# g3d2_ctrl_2.net
KiCad netlist of a schematic drawn in EAGLE
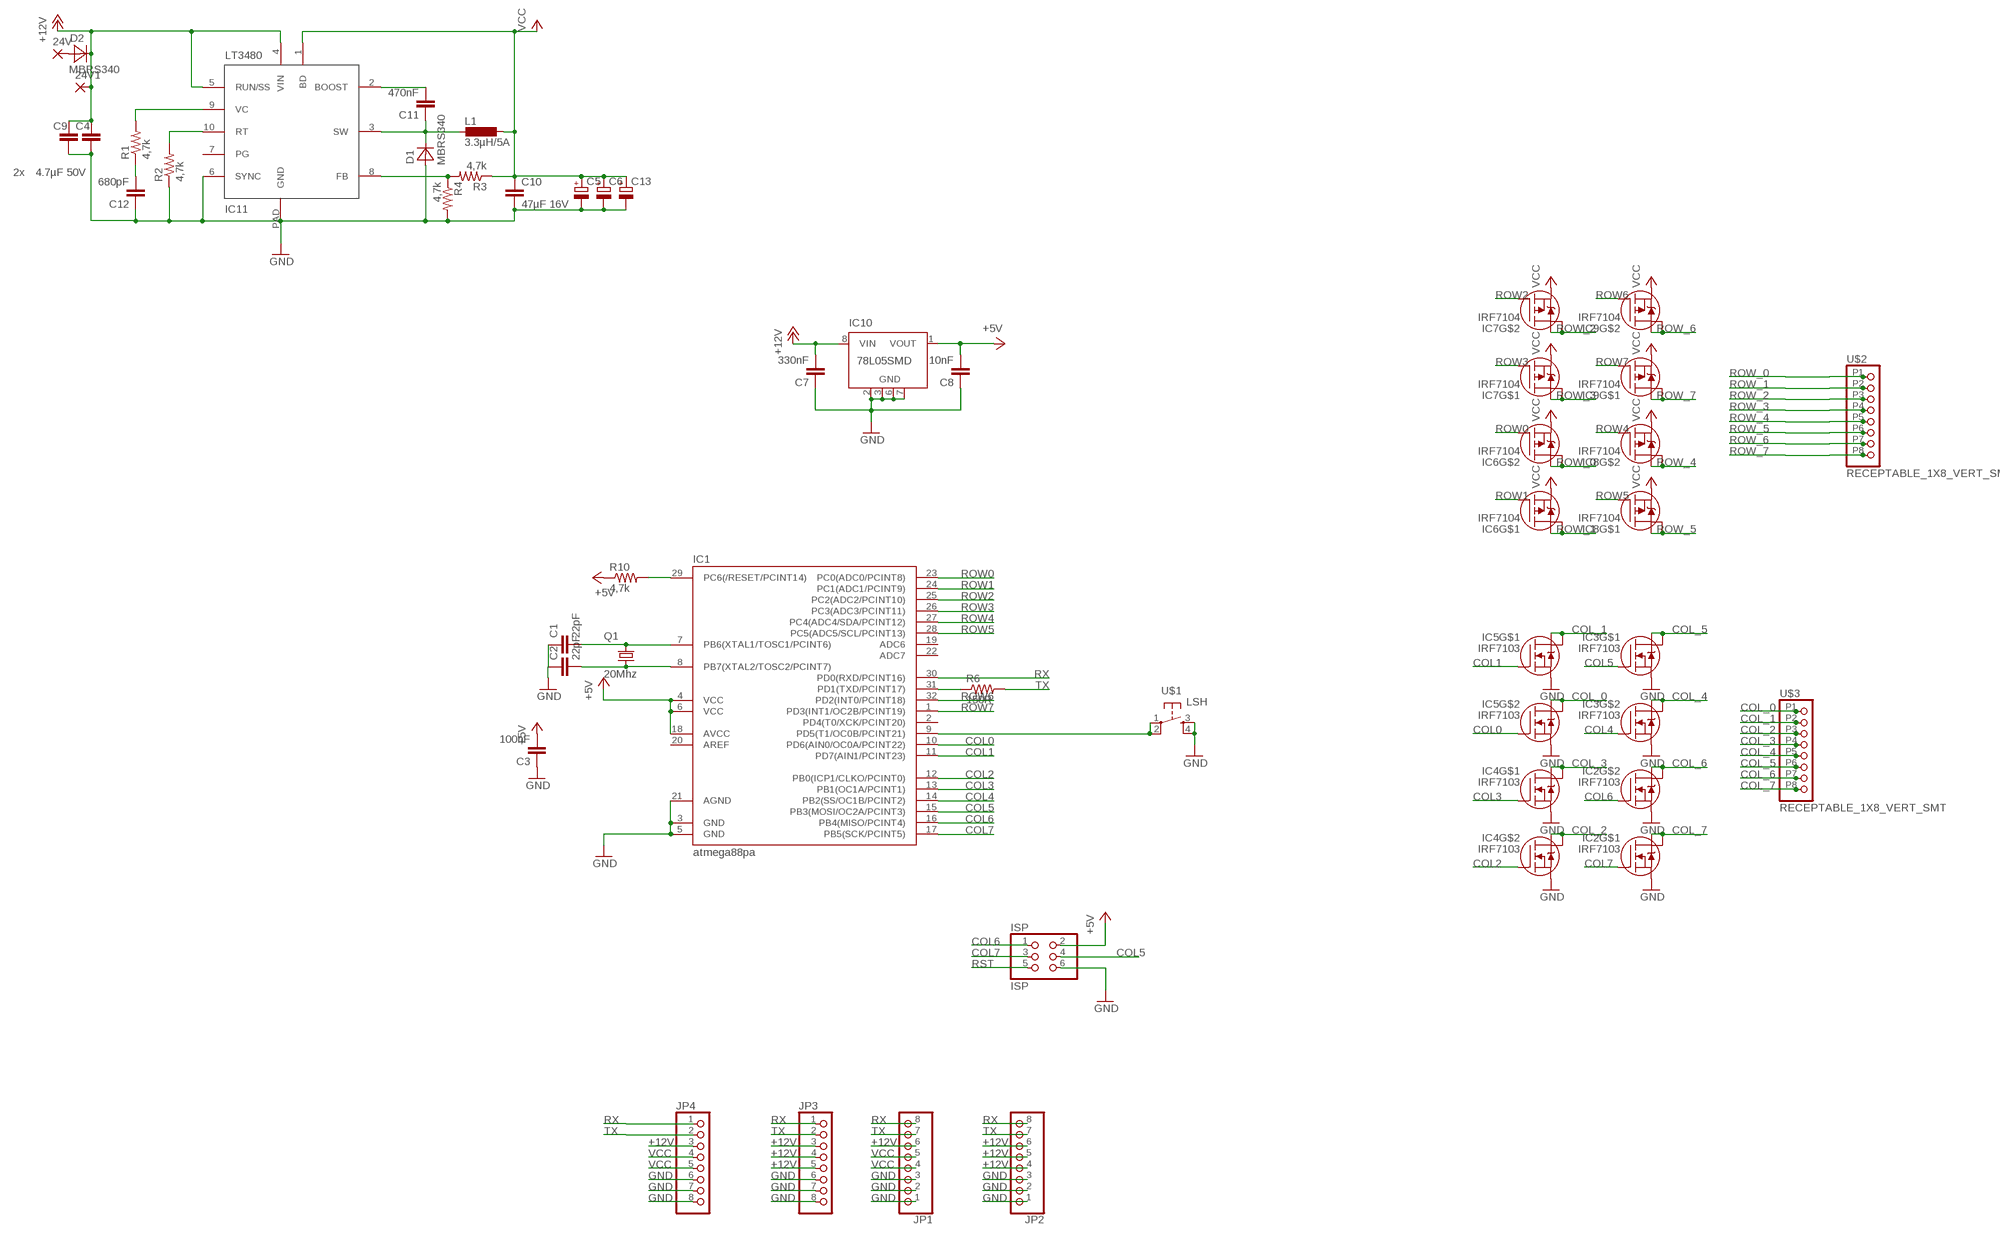
[diagram p0: schematic, sheet 1]

(export (version "E")
  (design (tool "Eeschema 10.0.6"))
  (components
    (comp (ref "24V")
      (value "SMD5")
      (footprint "eagle-import:SMD2,54-5,08")
      (libsource (lib "eagle-import") (part "SMD5"))
    )
    (comp (ref "24V1")
      (value "SMD5")
      (footprint "eagle-import:SMD2,54-5,08")
      (libsource (lib "eagle-import") (part "SMD5"))
    )
    (comp (ref "C1")
      (value "22pF")
      (footprint "eagle-import:0805")
      (libsource (lib "eagle-import") (part "CAP0805"))
    )
    (comp (ref "C2")
      (value "22pF")
      (footprint "eagle-import:0805")
      (libsource (lib "eagle-import") (part "CAP0805"))
    )
    (comp (ref "C3")
      (value "100nF")
      (footprint "eagle-import:0805")
      (libsource (lib "eagle-import") (part "CAP0805"))
    )
    (comp (ref "C4")
      (value "4.7µF 50V")
      (footprint "eagle-import:1210")
      (libsource (lib "eagle-import") (part "CAP1210"))
    )
    (comp (ref "C5")
      (value "CPOL-EUSMCD")
      (footprint "eagle-import:SMC_D")
      (libsource (lib "eagle-import") (part "CPOL-EUSMCD"))
    )
    (comp (ref "C6")
      (value "CPOL-EUSMCD")
      (footprint "eagle-import:SMC_D")
      (libsource (lib "eagle-import") (part "CPOL-EUSMCD"))
    )
    (comp (ref "C7")
      (value "330nF")
      (footprint "eagle-import:0805")
      (libsource (lib "eagle-import") (part "CAP0805"))
    )
    (comp (ref "C8")
      (value "10nF")
      (footprint "eagle-import:0805")
      (libsource (lib "eagle-import") (part "CAP0805"))
    )
    (comp (ref "C9")
      (value "4.7µF 50V")
      (footprint "eagle-import:1210")
      (libsource (lib "eagle-import") (part "CAP1210"))
    )
    (comp (ref "C10")
      (value "47µF 16V")
      (footprint "eagle-import:1210")
      (libsource (lib "eagle-import") (part "CAP1210"))
    )
    (comp (ref "C11")
      (value "470nF")
      (footprint "eagle-import:0805")
      (libsource (lib "eagle-import") (part "CAP0805"))
    )
    (comp (ref "C12")
      (value "680pF")
      (footprint "eagle-import:0805")
      (libsource (lib "eagle-import") (part "CAP0805"))
    )
    (comp (ref "C13")
      (value "CPOL-EUSMCD")
      (footprint "eagle-import:SMC_D")
      (libsource (lib "eagle-import") (part "CPOL-EUSMCD"))
    )
    (comp (ref "D1")
      (value "MBRS340")
      (footprint "eagle-import:DO214AB")
      (libsource (lib "eagle-import") (part "MBRS340"))
    )
    (comp (ref "D2")
      (value "MBRS340")
      (footprint "eagle-import:DO214AB")
      (libsource (lib "eagle-import") (part "MBRS340"))
    )
    (comp (ref "IC1")
      (value "atmega88pa")
      (footprint "eagle-import:TQFP32-08")
      (libsource (lib "eagle-import") (part "MEGA48/88/168-AU"))
    )
    (comp (ref "IC2")
      (value "IRF7103")
      (footprint "eagle-import:SO8-2")
      (libsource (lib "eagle-import") (part "IRF7103"))
    )
    (comp (ref "IC3")
      (value "IRF7103")
      (footprint "eagle-import:SO8-2")
      (libsource (lib "eagle-import") (part "IRF7103"))
    )
    (comp (ref "IC4")
      (value "IRF7103")
      (footprint "eagle-import:SO8-2")
      (libsource (lib "eagle-import") (part "IRF7103"))
    )
    (comp (ref "IC5")
      (value "IRF7103")
      (footprint "eagle-import:SO8-2")
      (libsource (lib "eagle-import") (part "IRF7103"))
    )
    (comp (ref "IC6")
      (value "IRF7104")
      (footprint "eagle-import:SO8-2")
      (libsource (lib "eagle-import") (part "IRF7104"))
    )
    (comp (ref "IC7")
      (value "IRF7104")
      (footprint "eagle-import:SO8-2")
      (libsource (lib "eagle-import") (part "IRF7104"))
    )
    (comp (ref "IC8")
      (value "IRF7104")
      (footprint "eagle-import:SO8-2")
      (libsource (lib "eagle-import") (part "IRF7104"))
    )
    (comp (ref "IC9")
      (value "IRF7104")
      (footprint "eagle-import:SO8-2")
      (libsource (lib "eagle-import") (part "IRF7104"))
    )
    (comp (ref "IC10")
      (value "78L05SMD")
      (footprint "eagle-import:SO08")
      (libsource (lib "eagle-import") (part "78LSMD05"))
    )
    (comp (ref "IC11")
      (value "LT3972")
      (footprint "eagle-import:MSOP10-PAD")
      (libsource (lib "eagle-import") (part "LT3480"))
    )
    (comp (ref "ISP")
      (value "ISP")
      (footprint "eagle-import:2X03")
      (libsource (lib "eagle-import") (part "PINHD-2X03_2.54"))
    )
    (comp (ref "JP1")
      (value "PINHD-1X08_2.54-SMD-90°")
      (footprint "eagle-import:1X08SMD_90")
      (libsource (lib "eagle-import") (part "PINHD-1X08_2.54-SMD-90°"))
    )
    (comp (ref "JP2")
      (value "PINHD-1X08_2.54-SMD-90°")
      (footprint "eagle-import:1X08SMD_90")
      (libsource (lib "eagle-import") (part "PINHD-1X08_2.54-SMD-90°"))
    )
    (comp (ref "JP3")
      (value "PINHD-1X08_2.54-SMD-90°")
      (footprint "eagle-import:1X08SMD_90")
      (libsource (lib "eagle-import") (part "PINHD-1X08_2.54-SMD-90°"))
    )
    (comp (ref "JP4")
      (value "PINHD-1X08_2.54-SMD-90°")
      (footprint "eagle-import:1X08SMD_90")
      (libsource (lib "eagle-import") (part "PINHD-1X08_2.54-SMD-90°"))
    )
    (comp (ref "L1")
      (value "3.3µH/5A")
      (footprint "eagle-import:DO3316P")
      (libsource (lib "eagle-import") (part "DO3316P"))
    )
    (comp (ref "Q1")
      (value "20Mhz")
      (footprint "eagle-import:X22")
      (libsource (lib "eagle-import") (part "X22-OSCILLATOR"))
    )
    (comp (ref "R1")
      (value "4,7k")
      (footprint "eagle-import:0805")
      (libsource (lib "eagle-import") (part "RESISTOR"))
    )
    (comp (ref "R2")
      (value "4,7k")
      (footprint "eagle-import:0805")
      (libsource (lib "eagle-import") (part "RESISTOR"))
    )
    (comp (ref "R3")
      (value "4,7k")
      (footprint "eagle-import:0805")
      (libsource (lib "eagle-import") (part "RESISTOR"))
    )
    (comp (ref "R4")
      (value "4,7k")
      (footprint "eagle-import:0805")
      (libsource (lib "eagle-import") (part "RESISTOR"))
    )
    (comp (ref "R6")
      (value "150R")
      (footprint "eagle-import:0805")
      (libsource (lib "eagle-import") (part "RESISTOR"))
    )
    (comp (ref "R10")
      (value "4,7k")
      (footprint "eagle-import:0805")
      (libsource (lib "eagle-import") (part "RESISTOR"))
    )
    (comp (ref "U$1")
      (value "LSH")
      (footprint "eagle-import:LSH")
      (libsource (lib "eagle-import") (part "LSH"))
    )
    (comp (ref "U$2")
      (value "RECEPTABLE_1X8_VERT_SMT")
      (footprint "eagle-import:RECEPTABLE_1X8_VERT_SMT")
      (libsource (lib "eagle-import") (part "RECEPTABLE_1X8_VERT_SMT"))
    )
    (comp (ref "U$3")
      (value "RECEPTABLE_1X8_VERT_SMT")
      (footprint "eagle-import:RECEPTABLE_1X8_VERT_SMT")
      (libsource (lib "eagle-import") (part "RECEPTABLE_1X8_VERT_SMT"))
    )
  )
  (nets
    (net (code "1") (name "+5V") (class "Default")
      (node (ref "C3") (pin "2") (pinfunction "2_2") (pintype "passive"))
      (node (ref "C8") (pin "2") (pinfunction "2_2") (pintype "passive"))
      (node (ref "IC1") (pin "18") (pinfunction "AVCC_18") (pintype "passive"))
      (node (ref "IC1") (pin "4") (pinfunction "VCC_4") (pintype "power_in"))
      (node (ref "IC1") (pin "6") (pinfunction "VCC_6") (pintype "power_in"))
      (node (ref "IC10") (pin "1") (pinfunction "VOUT_1") (pintype "output"))
      (node (ref "ISP") (pin "2") (pinfunction "2_2") (pintype "passive"))
      (node (ref "R10") (pin "1") (pinfunction "1_1") (pintype "passive"))
    )
    (net (code "2") (name "+12V") (class "Default")
      (node (ref "24V1") (pin "1") (pinfunction "P_1") (pintype "passive"))
      (node (ref "C4") (pin "1") (pinfunction "1_1") (pintype "passive"))
      (node (ref "C7") (pin "2") (pinfunction "2_2") (pintype "passive"))
      (node (ref "C9") (pin "1") (pinfunction "1_1") (pintype "passive"))
      (node (ref "D2") (pin "K") (pinfunction "C_K") (pintype "passive"))
      (node (ref "IC10") (pin "8") (pinfunction "VIN_8") (pintype "passive"))
      (node (ref "IC11") (pin "4") (pinfunction "VIN_4") (pintype "bidirectional"))
      (node (ref "IC11") (pin "5") (pinfunction "RUN/SS_5") (pintype "bidirectional"))
      (node (ref "JP1") (pin "6") (pinfunction "6_6") (pintype "passive"))
      (node (ref "JP2") (pin "4") (pinfunction "4_4") (pintype "passive"))
      (node (ref "JP2") (pin "5") (pinfunction "5_5") (pintype "passive"))
      (node (ref "JP2") (pin "6") (pinfunction "6_6") (pintype "passive"))
      (node (ref "JP3") (pin "3") (pinfunction "3_3") (pintype "passive"))
      (node (ref "JP3") (pin "4") (pinfunction "4_4") (pintype "passive"))
      (node (ref "JP3") (pin "5") (pinfunction "5_5") (pintype "passive"))
      (node (ref "JP4") (pin "3") (pinfunction "3_3") (pintype "passive"))
    )
    (net (code "3") (name "/COL0") (class "Default")
      (node (ref "IC1") (pin "10") (pinfunction "PD6(AIN0/OC0A/PCINT22)_10") (pintype "bidirectional"))
      (node (ref "IC5") (pin "4") (pinfunction "G_4") (pintype "bidirectional"))
    )
    (net (code "4") (name "/COL1") (class "Default")
      (node (ref "IC1") (pin "11") (pinfunction "PD7(AIN1/PCINT23)_11") (pintype "bidirectional"))
      (node (ref "IC5") (pin "2") (pinfunction "G_2") (pintype "bidirectional"))
    )
    (net (code "5") (name "/COL2") (class "Default")
      (node (ref "IC1") (pin "12") (pinfunction "PB0(ICP1/CLKO/PCINT0)_12") (pintype "bidirectional"))
      (node (ref "IC4") (pin "4") (pinfunction "G_4") (pintype "bidirectional"))
    )
    (net (code "6") (name "/COL3") (class "Default")
      (node (ref "IC1") (pin "13") (pinfunction "PB1(OC1A/PCINT1)_13") (pintype "bidirectional"))
      (node (ref "IC4") (pin "2") (pinfunction "G_2") (pintype "bidirectional"))
    )
    (net (code "7") (name "/COL4") (class "Default")
      (node (ref "IC1") (pin "14") (pinfunction "PB2(SS/OC1B/PCINT2)_14") (pintype "bidirectional"))
      (node (ref "IC3") (pin "4") (pinfunction "G_4") (pintype "bidirectional"))
    )
    (net (code "8") (name "/COL5") (class "Default")
      (node (ref "IC1") (pin "15") (pinfunction "PB3(MOSI/OC2A/PCINT3)_15") (pintype "bidirectional"))
      (node (ref "IC3") (pin "2") (pinfunction "G_2") (pintype "bidirectional"))
      (node (ref "ISP") (pin "4") (pinfunction "4_4") (pintype "passive"))
    )
    (net (code "9") (name "/COL6") (class "Default")
      (node (ref "IC1") (pin "16") (pinfunction "PB4(MISO/PCINT4)_16") (pintype "bidirectional"))
      (node (ref "IC2") (pin "4") (pinfunction "G_4") (pintype "bidirectional"))
      (node (ref "ISP") (pin "1") (pinfunction "1_1") (pintype "passive"))
    )
    (net (code "10") (name "/COL7") (class "Default")
      (node (ref "IC1") (pin "17") (pinfunction "PB5(SCK/PCINT5)_17") (pintype "bidirectional"))
      (node (ref "IC2") (pin "2") (pinfunction "G_2") (pintype "bidirectional"))
      (node (ref "ISP") (pin "3") (pinfunction "3_3") (pintype "passive"))
    )
    (net (code "11") (name "/COL_0") (class "Default")
      (node (ref "IC5") (pin "5") (pinfunction "D_5") (pintype "bidirectional"))
      (node (ref "IC5") (pin "6") (pinfunction "D_6") (pintype "bidirectional"))
      (node (ref "U$3") (pin "P1") (pinfunction "1_P1") (pintype "passive"))
    )
    (net (code "12") (name "/COL_1") (class "Default")
      (node (ref "IC5") (pin "7") (pinfunction "D_7") (pintype "bidirectional"))
      (node (ref "IC5") (pin "8") (pinfunction "D_8") (pintype "bidirectional"))
      (node (ref "U$3") (pin "P2") (pinfunction "2_P2") (pintype "passive"))
    )
    (net (code "13") (name "/COL_2") (class "Default")
      (node (ref "IC4") (pin "5") (pinfunction "D_5") (pintype "bidirectional"))
      (node (ref "IC4") (pin "6") (pinfunction "D_6") (pintype "bidirectional"))
      (node (ref "U$3") (pin "P3") (pinfunction "3_P3") (pintype "passive"))
    )
    (net (code "14") (name "/COL_3") (class "Default")
      (node (ref "IC4") (pin "7") (pinfunction "D_7") (pintype "bidirectional"))
      (node (ref "IC4") (pin "8") (pinfunction "D_8") (pintype "bidirectional"))
      (node (ref "U$3") (pin "P4") (pinfunction "4_P4") (pintype "passive"))
    )
    (net (code "15") (name "/COL_4") (class "Default")
      (node (ref "IC3") (pin "5") (pinfunction "D_5") (pintype "bidirectional"))
      (node (ref "IC3") (pin "6") (pinfunction "D_6") (pintype "bidirectional"))
      (node (ref "U$3") (pin "P5") (pinfunction "5_P5") (pintype "passive"))
    )
    (net (code "16") (name "/COL_5") (class "Default")
      (node (ref "IC3") (pin "7") (pinfunction "D_7") (pintype "bidirectional"))
      (node (ref "IC3") (pin "8") (pinfunction "D_8") (pintype "bidirectional"))
      (node (ref "U$3") (pin "P6") (pinfunction "6_P6") (pintype "passive"))
    )
    (net (code "17") (name "/COL_6") (class "Default")
      (node (ref "IC2") (pin "5") (pinfunction "D_5") (pintype "bidirectional"))
      (node (ref "IC2") (pin "6") (pinfunction "D_6") (pintype "bidirectional"))
      (node (ref "U$3") (pin "P7") (pinfunction "7_P7") (pintype "passive"))
    )
    (net (code "18") (name "/COL_7") (class "Default")
      (node (ref "IC2") (pin "7") (pinfunction "D_7") (pintype "bidirectional"))
      (node (ref "IC2") (pin "8") (pinfunction "D_8") (pintype "bidirectional"))
      (node (ref "U$3") (pin "P8") (pinfunction "8_P8") (pintype "passive"))
    )
    (net (code "19") (name "/ROW0") (class "Default")
      (node (ref "IC1") (pin "23") (pinfunction "PC0(ADC0/PCINT8)_23") (pintype "bidirectional"))
      (node (ref "IC6") (pin "4") (pinfunction "G_4") (pintype "bidirectional"))
    )
    (net (code "20") (name "/ROW1") (class "Default")
      (node (ref "IC1") (pin "24") (pinfunction "PC1(ADC1/PCINT9)_24") (pintype "bidirectional"))
      (node (ref "IC6") (pin "2") (pinfunction "G_2") (pintype "bidirectional"))
    )
    (net (code "21") (name "/ROW2") (class "Default")
      (node (ref "IC1") (pin "25") (pinfunction "PC2(ADC2/PCINT10)_25") (pintype "bidirectional"))
      (node (ref "IC7") (pin "4") (pinfunction "G_4") (pintype "bidirectional"))
    )
    (net (code "22") (name "/ROW3") (class "Default")
      (node (ref "IC1") (pin "26") (pinfunction "PC3(ADC3/PCINT11)_26") (pintype "bidirectional"))
      (node (ref "IC7") (pin "2") (pinfunction "G_2") (pintype "bidirectional"))
    )
    (net (code "23") (name "/ROW4") (class "Default")
      (node (ref "IC1") (pin "27") (pinfunction "PC4(ADC4/SDA/PCINT12)_27") (pintype "bidirectional"))
      (node (ref "IC8") (pin "4") (pinfunction "G_4") (pintype "bidirectional"))
    )
    (net (code "24") (name "/ROW5") (class "Default")
      (node (ref "IC1") (pin "28") (pinfunction "PC5(ADC5/SCL/PCINT13)_28") (pintype "bidirectional"))
      (node (ref "IC8") (pin "2") (pinfunction "G_2") (pintype "bidirectional"))
    )
    (net (code "25") (name "/ROW6") (class "Default")
      (node (ref "IC1") (pin "32") (pinfunction "PD2(INT0/PCINT18)_32") (pintype "bidirectional"))
      (node (ref "IC9") (pin "4") (pinfunction "G_4") (pintype "bidirectional"))
    )
    (net (code "26") (name "/ROW7") (class "Default")
      (node (ref "IC1") (pin "1") (pinfunction "PD3(INT1/OC2B/PCINT19)_1") (pintype "bidirectional"))
      (node (ref "IC9") (pin "2") (pinfunction "G_2") (pintype "bidirectional"))
    )
    (net (code "27") (name "/ROW_0") (class "Default")
      (node (ref "IC6") (pin "5") (pinfunction "D_5") (pintype "bidirectional"))
      (node (ref "IC6") (pin "6") (pinfunction "D_6") (pintype "bidirectional"))
      (node (ref "U$2") (pin "P1") (pinfunction "1_P1") (pintype "passive"))
    )
    (net (code "28") (name "/ROW_1") (class "Default")
      (node (ref "IC6") (pin "7") (pinfunction "D_7") (pintype "bidirectional"))
      (node (ref "IC6") (pin "8") (pinfunction "D_8") (pintype "bidirectional"))
      (node (ref "U$2") (pin "P2") (pinfunction "2_P2") (pintype "passive"))
    )
    (net (code "29") (name "/ROW_2") (class "Default")
      (node (ref "IC7") (pin "5") (pinfunction "D_5") (pintype "bidirectional"))
      (node (ref "IC7") (pin "6") (pinfunction "D_6") (pintype "bidirectional"))
      (node (ref "U$2") (pin "P3") (pinfunction "3_P3") (pintype "passive"))
    )
    (net (code "30") (name "/ROW_3") (class "Default")
      (node (ref "IC7") (pin "7") (pinfunction "D_7") (pintype "bidirectional"))
      (node (ref "IC7") (pin "8") (pinfunction "D_8") (pintype "bidirectional"))
      (node (ref "U$2") (pin "P4") (pinfunction "4_P4") (pintype "passive"))
    )
    (net (code "31") (name "/ROW_4") (class "Default")
      (node (ref "IC8") (pin "5") (pinfunction "D_5") (pintype "bidirectional"))
      (node (ref "IC8") (pin "6") (pinfunction "D_6") (pintype "bidirectional"))
      (node (ref "U$2") (pin "P5") (pinfunction "5_P5") (pintype "passive"))
    )
    (net (code "32") (name "/ROW_5") (class "Default")
      (node (ref "IC8") (pin "7") (pinfunction "D_7") (pintype "bidirectional"))
      (node (ref "IC8") (pin "8") (pinfunction "D_8") (pintype "bidirectional"))
      (node (ref "U$2") (pin "P6") (pinfunction "6_P6") (pintype "passive"))
    )
    (net (code "33") (name "/ROW_6") (class "Default")
      (node (ref "IC9") (pin "5") (pinfunction "D_5") (pintype "bidirectional"))
      (node (ref "IC9") (pin "6") (pinfunction "D_6") (pintype "bidirectional"))
      (node (ref "U$2") (pin "P7") (pinfunction "7_P7") (pintype "passive"))
    )
    (net (code "34") (name "/ROW_7") (class "Default")
      (node (ref "IC9") (pin "7") (pinfunction "D_7") (pintype "bidirectional"))
      (node (ref "IC9") (pin "8") (pinfunction "D_8") (pintype "bidirectional"))
      (node (ref "U$2") (pin "P8") (pinfunction "8_P8") (pintype "passive"))
    )
    (net (code "35") (name "/RST") (class "Default")
      (node (ref "IC1") (pin "29") (pinfunction "PC6(/RESET/PCINT14)_29") (pintype "bidirectional"))
      (node (ref "ISP") (pin "5") (pinfunction "5_5") (pintype "passive"))
      (node (ref "R10") (pin "2") (pinfunction "2_2") (pintype "passive"))
    )
    (net (code "36") (name "/RX") (class "Default")
      (node (ref "IC1") (pin "30") (pinfunction "PD0(RXD/PCINT16)_30") (pintype "bidirectional"))
      (node (ref "JP1") (pin "8") (pinfunction "8_8") (pintype "passive"))
      (node (ref "JP2") (pin "8") (pinfunction "8_8") (pintype "passive"))
      (node (ref "JP3") (pin "1") (pinfunction "1_1") (pintype "passive"))
      (node (ref "JP4") (pin "1") (pinfunction "1_1") (pintype "passive"))
    )
    (net (code "37") (name "/TX") (class "Default")
      (node (ref "JP1") (pin "7") (pinfunction "7_7") (pintype "passive"))
      (node (ref "JP2") (pin "7") (pinfunction "7_7") (pintype "passive"))
      (node (ref "JP3") (pin "2") (pinfunction "2_2") (pintype "passive"))
      (node (ref "JP4") (pin "2") (pinfunction "2_2") (pintype "passive"))
      (node (ref "R6") (pin "2") (pinfunction "2_2") (pintype "passive"))
    )
    (net (code "38") (name "GND") (class "Default")
      (node (ref "C1") (pin "1") (pinfunction "1_1") (pintype "passive"))
      (node (ref "C10") (pin "2") (pinfunction "2_2") (pintype "passive"))
      (node (ref "C12") (pin "1") (pinfunction "1_1") (pintype "passive"))
      (node (ref "C13") (pin "-") (pinfunction "-_-") (pintype "passive"))
      (node (ref "C2") (pin "1") (pinfunction "1_1") (pintype "passive"))
      (node (ref "C3") (pin "1") (pinfunction "1_1") (pintype "passive"))
      (node (ref "C4") (pin "2") (pinfunction "2_2") (pintype "passive"))
      (node (ref "C5") (pin "-") (pinfunction "-_-") (pintype "passive"))
      (node (ref "C6") (pin "-") (pinfunction "-_-") (pintype "passive"))
      (node (ref "C7") (pin "1") (pinfunction "1_1") (pintype "passive"))
      (node (ref "C8") (pin "1") (pinfunction "1_1") (pintype "passive"))
      (node (ref "C9") (pin "2") (pinfunction "2_2") (pintype "passive"))
      (node (ref "D1") (pin "A") (pinfunction "A_A") (pintype "passive"))
      (node (ref "IC1") (pin "21") (pinfunction "AGND_21") (pintype "power_in"))
      (node (ref "IC1") (pin "3") (pinfunction "GND_3") (pintype "power_in"))
      (node (ref "IC1") (pin "5") (pinfunction "GND_5") (pintype "power_in"))
      (node (ref "IC10") (pin "2") (pinfunction "GND_2") (pintype "power_in"))
      (node (ref "IC10") (pin "3") (pinfunction "GND_3") (pintype "power_in"))
      (node (ref "IC10") (pin "6") (pinfunction "GND_6") (pintype "power_in"))
      (node (ref "IC10") (pin "7") (pinfunction "GND_7") (pintype "power_in"))
      (node (ref "IC11") (pin "6") (pinfunction "SYNC_6") (pintype "bidirectional"))
      (node (ref "IC11") (pin "PAD") (pinfunction "GND_PAD") (pintype "bidirectional"))
      (node (ref "IC2") (pin "1") (pinfunction "S_1") (pintype "bidirectional"))
      (node (ref "IC2") (pin "3") (pinfunction "S_3") (pintype "bidirectional"))
      (node (ref "IC3") (pin "1") (pinfunction "S_1") (pintype "bidirectional"))
      (node (ref "IC3") (pin "3") (pinfunction "S_3") (pintype "bidirectional"))
      (node (ref "IC4") (pin "1") (pinfunction "S_1") (pintype "bidirectional"))
      (node (ref "IC4") (pin "3") (pinfunction "S_3") (pintype "bidirectional"))
      (node (ref "IC5") (pin "1") (pinfunction "S_1") (pintype "bidirectional"))
      (node (ref "IC5") (pin "3") (pinfunction "S_3") (pintype "bidirectional"))
      (node (ref "ISP") (pin "6") (pinfunction "6_6") (pintype "passive"))
      (node (ref "JP1") (pin "1") (pinfunction "1_1") (pintype "passive"))
      (node (ref "JP1") (pin "2") (pinfunction "2_2") (pintype "passive"))
      (node (ref "JP1") (pin "3") (pinfunction "3_3") (pintype "passive"))
      (node (ref "JP2") (pin "1") (pinfunction "1_1") (pintype "passive"))
      (node (ref "JP2") (pin "2") (pinfunction "2_2") (pintype "passive"))
      (node (ref "JP2") (pin "3") (pinfunction "3_3") (pintype "passive"))
      (node (ref "JP3") (pin "6") (pinfunction "6_6") (pintype "passive"))
      (node (ref "JP3") (pin "7") (pinfunction "7_7") (pintype "passive"))
      (node (ref "JP3") (pin "8") (pinfunction "8_8") (pintype "passive"))
      (node (ref "JP4") (pin "6") (pinfunction "6_6") (pintype "passive"))
      (node (ref "JP4") (pin "7") (pinfunction "7_7") (pintype "passive"))
      (node (ref "JP4") (pin "8") (pinfunction "8_8") (pintype "passive"))
      (node (ref "R2") (pin "1") (pinfunction "1_1") (pintype "passive"))
      (node (ref "R4") (pin "2") (pinfunction "2_2") (pintype "passive"))
      (node (ref "U$1") (pin "3") (pinfunction "3_3") (pintype "passive"))
      (node (ref "U$1") (pin "4") (pinfunction "4_4") (pintype "passive"))
    )
    (net (code "39") (name "Net-(24V-P)") (class "Default")
      (node (ref "24V") (pin "1") (pinfunction "P_1") (pintype "passive"))
      (node (ref "D2") (pin "A") (pinfunction "A_A") (pintype "passive"))
    )
    (net (code "40") (name "Net-(C12-Pad2)") (class "Default")
      (node (ref "C12") (pin "2") (pinfunction "2_2") (pintype "passive"))
      (node (ref "R1") (pin "1") (pinfunction "1_1") (pintype "passive"))
    )
    (net (code "41") (name "Net-(D1-C)") (class "Default")
      (node (ref "C11") (pin "1") (pinfunction "1_1") (pintype "passive"))
      (node (ref "D1") (pin "K") (pinfunction "C_K") (pintype "passive"))
      (node (ref "IC11") (pin "3") (pinfunction "SW_3") (pintype "bidirectional"))
      (node (ref "L1") (pin "1") (pinfunction "1_1") (pintype "passive"))
    )
    (net (code "42") (name "Net-(IC1-PB6(XTAL1{slash}TOSC1{slash}PCINT6))") (class "Default")
      (node (ref "C1") (pin "2") (pinfunction "2_2") (pintype "passive"))
      (node (ref "IC1") (pin "7") (pinfunction "PB6(XTAL1/TOSC1/PCINT6)_7") (pintype "bidirectional"))
      (node (ref "Q1") (pin "3") (pinfunction "2_3") (pintype "passive"))
    )
    (net (code "43") (name "Net-(IC1-PB7(XTAL2{slash}TOSC2{slash}PCINT7))") (class "Default")
      (node (ref "C2") (pin "2") (pinfunction "2_2") (pintype "passive"))
      (node (ref "IC1") (pin "8") (pinfunction "PB7(XTAL2/TOSC2/PCINT7)_8") (pintype "bidirectional"))
      (node (ref "Q1") (pin "1") (pinfunction "1_1") (pintype "passive"))
    )
    (net (code "44") (name "Net-(IC1-PD1(TXD{slash}PCINT17))") (class "Default")
      (node (ref "IC1") (pin "31") (pinfunction "PD1(TXD/PCINT17)_31") (pintype "bidirectional"))
      (node (ref "R6") (pin "1") (pinfunction "1_1") (pintype "passive"))
    )
    (net (code "45") (name "Net-(IC1-PD5(T1{slash}OC0B{slash}PCINT21))") (class "Default")
      (node (ref "IC1") (pin "9") (pinfunction "PD5(T1/OC0B/PCINT21)_9") (pintype "bidirectional"))
      (node (ref "U$1") (pin "1") (pinfunction "1_1") (pintype "passive"))
      (node (ref "U$1") (pin "2") (pinfunction "2_2") (pintype "passive"))
    )
    (net (code "46") (name "Net-(IC11-BOOST)") (class "Default")
      (node (ref "C11") (pin "2") (pinfunction "2_2") (pintype "passive"))
      (node (ref "IC11") (pin "2") (pinfunction "BOOST_2") (pintype "bidirectional"))
    )
    (net (code "47") (name "Net-(IC11-FB)") (class "Default")
      (node (ref "IC11") (pin "8") (pinfunction "FB_8") (pintype "bidirectional"))
      (node (ref "R3") (pin "2") (pinfunction "2_2") (pintype "passive"))
      (node (ref "R4") (pin "1") (pinfunction "1_1") (pintype "passive"))
    )
    (net (code "48") (name "Net-(IC11-RT)") (class "Default")
      (node (ref "IC11") (pin "10") (pinfunction "RT_10") (pintype "bidirectional"))
      (node (ref "R2") (pin "2") (pinfunction "2_2") (pintype "passive"))
    )
    (net (code "49") (name "Net-(IC11-VC)") (class "Default")
      (node (ref "IC11") (pin "9") (pinfunction "VC_9") (pintype "bidirectional"))
      (node (ref "R1") (pin "2") (pinfunction "2_2") (pintype "passive"))
    )
    (net (code "50") (name "VCC") (class "Default")
      (node (ref "C10") (pin "1") (pinfunction "1_1") (pintype "passive"))
      (node (ref "C13") (pin "+") (pinfunction "+_+") (pintype "passive"))
      (node (ref "C5") (pin "+") (pinfunction "+_+") (pintype "passive"))
      (node (ref "C6") (pin "+") (pinfunction "+_+") (pintype "passive"))
      (node (ref "IC11") (pin "1") (pinfunction "BD_1") (pintype "bidirectional"))
      (node (ref "IC6") (pin "1") (pinfunction "S_1") (pintype "bidirectional"))
      (node (ref "IC6") (pin "3") (pinfunction "S_3") (pintype "bidirectional"))
      (node (ref "IC7") (pin "1") (pinfunction "S_1") (pintype "bidirectional"))
      (node (ref "IC7") (pin "3") (pinfunction "S_3") (pintype "bidirectional"))
      (node (ref "IC8") (pin "1") (pinfunction "S_1") (pintype "bidirectional"))
      (node (ref "IC8") (pin "3") (pinfunction "S_3") (pintype "bidirectional"))
      (node (ref "IC9") (pin "1") (pinfunction "S_1") (pintype "bidirectional"))
      (node (ref "IC9") (pin "3") (pinfunction "S_3") (pintype "bidirectional"))
      (node (ref "JP1") (pin "4") (pinfunction "4_4") (pintype "passive"))
      (node (ref "JP1") (pin "5") (pinfunction "5_5") (pintype "passive"))
      (node (ref "JP4") (pin "4") (pinfunction "4_4") (pintype "passive"))
      (node (ref "JP4") (pin "5") (pinfunction "5_5") (pintype "passive"))
      (node (ref "L1") (pin "2") (pinfunction "2_2") (pintype "passive"))
      (node (ref "R3") (pin "1") (pinfunction "1_1") (pintype "passive"))
    )
    (net (code "51") (name "unconnected-(IC1-ADC6-Pad19)") (class "Default")
      (node (ref "IC1") (pin "19") (pinfunction "ADC6_19") (pintype "passive"))
    )
    (net (code "52") (name "unconnected-(IC1-ADC7-Pad22)") (class "Default")
      (node (ref "IC1") (pin "22") (pinfunction "ADC7_22") (pintype "passive"))
    )
    (net (code "53") (name "unconnected-(IC1-AREF-Pad20)") (class "Default")
      (node (ref "IC1") (pin "20") (pinfunction "AREF_20") (pintype "passive"))
    )
    (net (code "54") (name "unconnected-(IC1-PD4(T0{slash}XCK{slash}PCINT20)-Pad2)") (class "Default")
      (node (ref "IC1") (pin "2") (pinfunction "PD4(T0/XCK/PCINT20)_2") (pintype "bidirectional"))
    )
    (net (code "55") (name "unconnected-(IC11-PG-Pad7)") (class "Default")
      (node (ref "IC11") (pin "7") (pinfunction "PG_7") (pintype "bidirectional"))
    )
  )
)
